# comms_uhf.net
KiCad netlist of a schematic drawn in Altium Designer
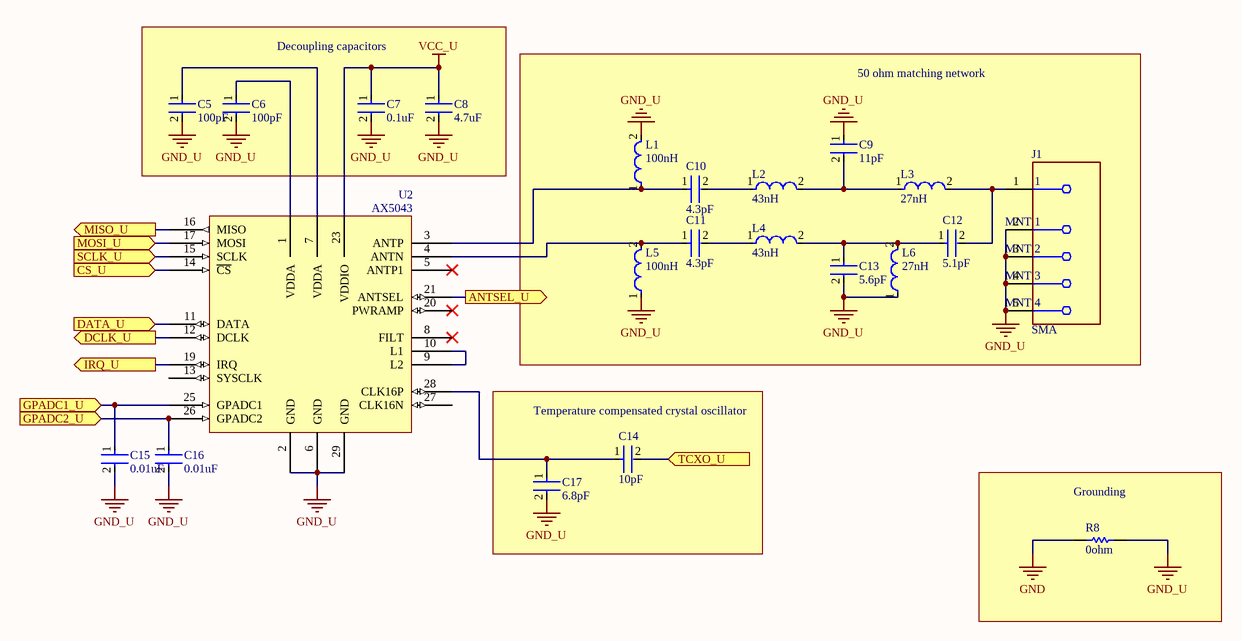
[diagram p0: comms_uhf.SchDoc]

(export (version "E")
  (design (tool "Eeschema 10.0.6"))
  (components
    (comp (ref "C5")
      (value "100pF")
      (footprint "FP-C0805C-DN-IPC_A")
      (description "Multilayer Ceramic Capacitors (MLCC) - SMD/SMT 100volts 100pF C0G 5%")
      (fields
        (field (name "MANUFACTURER") "KEMET")
        (field (name "MANUFACTURER PART NUMBER") "C0805C101J1GACTU")
      )
      (libsource (lib "WEST_Schematic_Library") (part "C0805C101J1GACTU"))
    )
    (comp (ref "C6")
      (value "100pF")
      (footprint "FP-C0805C-DN-IPC_A")
      (description "Multilayer Ceramic Capacitors (MLCC) - SMD/SMT 100volts 100pF C0G 5%")
      (fields
        (field (name "MANUFACTURER") "KEMET")
        (field (name "MANUFACTURER PART NUMBER") "C0805C101J1GACTU")
      )
      (libsource (lib "WEST_Schematic_Library") (part "C0805C101J1GACTU"))
    )
    (comp (ref "C7")
      (value "0.1uF")
      (footprint "FP-C0805C-DN-IPC_A")
      (description "Cap Ceramic 0.1uF 50V X7R 10% SMD 2.0 x 1.2 mm 125 C Paper T/R")
      (fields
        (field (name "MANUFACTURER") "KEMET")
        (field (name "MANUFACTURER PART NUMBER") "C0805C104K5RACTU")
      )
      (libsource (lib "WEST_Schematic_Library") (part "C0805C104K5RACTU"))
    )
    (comp (ref "C8")
      (value "4.7uF")
      (footprint "FP-C0805C-DN-IPC_A")
      (description "Cap Ceramic 4.7uF 25V X5R 10% SMD 0805 85°C Plastic T/R")
      (fields
        (field (name "MANUFACTURER") "KEMET")
        (field (name "MANUFACTURER PART NUMBER") "C0805C475K3PACTU")
      )
      (libsource (lib "WEST_Schematic_Library") (part "C0805C475K3PACTU"))
    )
    (comp (ref "C9")
      (value "11pF")
      (footprint "FP-C0805C-DN-IPC_A")
      (description "Cap Ceramic 11pF 50V C0G 5% SMD 0805 125°C Plastic T/R")
      (fields
        (field (name "MANUFACTURER") "KEMET")
        (field (name "MANUFACTURER PART NUMBER") "C0805C110J5GACTU")
      )
      (libsource (lib "WEST_Schematic_Library") (part "C0805C110J5GACTU"))
    )
    (comp (ref "C10")
      (value "4.3pF")
      (footprint "FP-C0805C-DN-IPC_A")
      (description "Cap Ceramic 4.3pF 100V C0G 0.5pF SMD 0805 125°C Paper T/R")
      (fields
        (field (name "MANUFACTURER") "KEMET")
        (field (name "MANUFACTURER PART NUMBER") "C0805C439D1GACTU")
      )
      (libsource (lib "WEST_Schematic_Library") (part "C0805C439D1GACTU"))
    )
    (comp (ref "C11")
      (value "4.3pF")
      (footprint "FP-C0805C-DN-IPC_A")
      (description "Cap Ceramic 4.3pF 100V C0G 0.5pF SMD 0805 125°C Paper T/R")
      (fields
        (field (name "MANUFACTURER") "KEMET")
        (field (name "MANUFACTURER PART NUMBER") "C0805C439D1GACTU")
      )
      (libsource (lib "WEST_Schematic_Library") (part "C0805C439D1GACTU"))
    )
    (comp (ref "C12")
      (value "5.1pF")
      (footprint "FP-C0805C-DN-IPC_A")
      (description "Cap Ceramic 5.1pF 50V C0G 0.25pF SMD 0805 125°C Paper T/R")
      (fields
        (field (name "MANUFACTURER") "KEMET")
        (field (name "MANUFACTURER PART NUMBER") "C0805C519C5GACTU")
      )
      (libsource (lib "WEST_Schematic_Library") (part "C0805C519C5GACTU"))
    )
    (comp (ref "C13")
      (value "5.6pF")
      (footprint "FP-C0805C-DN-IPC_A")
      (description "Cap Ceramic 5.6pF 50V C0G 0.5pF SMD 0805 125°C Plastic T/R")
      (fields
        (field (name "MANUFACTURER") "KEMET")
        (field (name "MANUFACTURER PART NUMBER") "C0805C569D5GACTU")
      )
      (libsource (lib "WEST_Schematic_Library") (part "C0805C569D5GACTU"))
    )
    (comp (ref "C14")
      (value "10pF")
      (footprint "FP-C0805C-DN-IPC_A")
      (description "Cap Ceramic 10pF 100V C0G 5% SMD 0805 125C Plastic T/R")
      (fields
        (field (name "MANUFACTURER") "KEMET")
        (field (name "MANUFACTURER PART NUMBER") "C0805C100J1GACTU")
      )
      (libsource (lib "WEST_Schematic_Library") (part "C0805C100J1GACTU"))
    )
    (comp (ref "C15")
      (value "0.01uF")
      (footprint "FP-C0805C-DN-IPC_A")
      (description "Cap Ceramic 0.01uF 50V X7R 10% SMD 0805 125C Plastic T/R")
      (fields
        (field (name "MANUFACTURER") "KEMET")
        (field (name "MANUFACTURER PART NUMBER") "C0805C103K5RAC-TU")
      )
      (libsource (lib "WEST_Schematic_Library") (part "C0805C103K5RAC-TU"))
    )
    (comp (ref "C16")
      (value "0.01uF")
      (footprint "FP-C0805C-DN-IPC_A")
      (description "Cap Ceramic 0.01uF 50V X7R 10% SMD 0805 125C Plastic T/R")
      (fields
        (field (name "MANUFACTURER") "KEMET")
        (field (name "MANUFACTURER PART NUMBER") "C0805C103K5RAC-TU")
      )
      (libsource (lib "WEST_Schematic_Library") (part "C0805C103K5RAC-TU"))
    )
    (comp (ref "C17")
      (value "6.8pF")
      (footprint "FP-C0805C-DN-IPC_A")
      (description "Cap Ceramic 6.8pF 50V C0G 0.5pF SMD 0805 125°C Plastic T/R")
      (fields
        (field (name "MANUFACTURER") "KEMET")
        (field (name "MANUFACTURER PART NUMBER") "C0805C689D5GACTU")
      )
      (libsource (lib "WEST_Schematic_Library") (part "C0805C689D5GACTU"))
    )
    (comp (ref "J1")
      (value "SMA")
      (footprint "FP-73251-1350-MFG")
      (description "RF Connectors / Coaxial Connectors SMA ST PCB-JCK STD SMT")
      (fields (field (name "MANUFACTURER") "Molex") (field (name "MANUFACTURER PART NUMBER") "73251-1350"))
      (libsource (lib "WEST_Schematic_Library") (part "73251-1350"))
    )
    (comp (ref "L1")
      (value "100nH")
      (footprint "FP-C0805C-DN-IPC_A")
      (description "Ind RF Chip Wirewound 100nH 5% 150MHz 65Q-Factor 400mA 0805 Embossed T/R")
      (fields
        (field (name "MANUFACTURER") "Murata")
        (field (name "MANUFACTURER PART NUMBER") "LQW2BASR10J00L")
      )
      (libsource (lib "WEST_Schematic_Library") (part "LQW2BASR10J00L"))
    )
    (comp (ref "L2")
      (value "43nH")
      (footprint "FP-C0805C-DN-IPC_A")
      (description "Ind RF Chip Wirewound 43nH 5% 200MHz 60Q-Factor 500mA 0805 Embossed T/R")
      (fields
        (field (name "MANUFACTURER") "Murata")
        (field (name "MANUFACTURER PART NUMBER") "LQW2BAS43NJ00L")
      )
      (libsource (lib "WEST_Schematic_Library") (part "LQW2BAS43NJ00L"))
    )
    (comp (ref "L3")
      (value "27nH")
      (footprint "FP-C0805C-DN-IPC_A")
      (description "Ind RF Chip Wirewound 27nH 0.5A ±5% 0805")
      (fields
        (field (name "MANUFACTURER") "Murata")
        (field (name "MANUFACTURER PART NUMBER") "LQW2BAS27NJ00L")
      )
      (libsource (lib "WEST_Schematic_Library") (part "LQW2BAS27NJ00L"))
    )
    (comp (ref "L4")
      (value "43nH")
      (footprint "FP-C0805C-DN-IPC_A")
      (description "Ind RF Chip Wirewound 43nH 5% 200MHz 60Q-Factor 500mA 0805 Embossed T/R")
      (fields
        (field (name "MANUFACTURER") "Murata")
        (field (name "MANUFACTURER PART NUMBER") "LQW2BAS43NJ00L")
      )
      (libsource (lib "WEST_Schematic_Library") (part "LQW2BAS43NJ00L"))
    )
    (comp (ref "L5")
      (value "100nH")
      (footprint "FP-C0805C-DN-IPC_A")
      (description "Ind RF Chip Wirewound 100nH 5% 150MHz 65Q-Factor 400mA 0805 Embossed T/R")
      (fields
        (field (name "MANUFACTURER") "Murata")
        (field (name "MANUFACTURER PART NUMBER") "LQW2BASR10J00L")
      )
      (libsource (lib "WEST_Schematic_Library") (part "LQW2BASR10J00L"))
    )
    (comp (ref "L6")
      (value "27nH")
      (footprint "FP-C0805C-DN-IPC_A")
      (description "Ind RF Chip Wirewound 27nH 0.5A ±5% 0805")
      (fields
        (field (name "MANUFACTURER") "Murata")
        (field (name "MANUFACTURER PART NUMBER") "LQW2BAS27NJ00L")
      )
      (libsource (lib "WEST_Schematic_Library") (part "LQW2BAS27NJ00L"))
    )
    (comp (ref "R8")
      (value "0ohm")
      (footprint "FP-C0805C-DN-IPC_A")
      (description "CRCW Series 0805 0.125 W 0 Ohm Jumper Surface Mount Thick Film Chip Resistor")
      (fields
        (field (name "MANUFACTURER") "Vishay")
        (field (name "MANUFACTURER PART NUMBER") "CRCW08050000Z0EA")
      )
      (libsource (lib "WEST_Schematic_Library") (part "CRCW08050000Z0EA"))
    )
    (comp (ref "U2")
      (value "AX5043")
      (footprint "QFN50P500X500X90_HS-29N")
      (description "Rf Transceiver ASK/AFSK/FM/FSK/4-FSK/GFSK/GMSK/MSK/PSK 1.8 V to 3.6V 28-PIN QFN T/r")
      (fields
        (field (name "MANUFACTURER") "ON Semiconductor")
        (field (name "MANUFACTURER PART NUMBER") "AX5043-1-TW30")
      )
      (libsource (lib "WEST_Schematic_Library") (part "AX5043-1-TW30"))
    )
  )
  (nets
    (net (code "1") (name "/ANTSEL_U") (class "Default")
      (node (ref "U2") (pin "21") (pinfunction "ANTSEL_21") (pintype "bidirectional"))
    )
    (net (code "2") (name "/CS_U") (class "Default")
      (node (ref "U2") (pin "14") (pinfunction "~{CS}_14") (pintype "input"))
    )
    (net (code "3") (name "/DATA_U") (class "Default")
      (node (ref "U2") (pin "11") (pinfunction "DATA_11") (pintype "bidirectional"))
    )
    (net (code "4") (name "/DCLK_U") (class "Default")
      (node (ref "U2") (pin "12") (pinfunction "DCLK_12") (pintype "bidirectional"))
    )
    (net (code "5") (name "/GPADC1_U") (class "Default")
      (node (ref "C15") (pin "1") (pinfunction "1_1") (pintype "passive"))
      (node (ref "U2") (pin "25") (pinfunction "GPADC1_25") (pintype "input"))
    )
    (net (code "6") (name "/GPADC2_U") (class "Default")
      (node (ref "C16") (pin "1") (pinfunction "1_1") (pintype "passive"))
      (node (ref "U2") (pin "26") (pinfunction "GPADC2_26") (pintype "input"))
    )
    (net (code "7") (name "/IRQ_U") (class "Default")
      (node (ref "U2") (pin "19") (pinfunction "IRQ_19") (pintype "bidirectional"))
    )
    (net (code "8") (name "/MISO_U") (class "Default")
      (node (ref "U2") (pin "16") (pinfunction "MISO_16") (pintype "output"))
    )
    (net (code "9") (name "/MOSI_U") (class "Default")
      (node (ref "U2") (pin "17") (pinfunction "MOSI_17") (pintype "input"))
    )
    (net (code "10") (name "/SCLK_U") (class "Default")
      (node (ref "U2") (pin "15") (pinfunction "SCLK_15") (pintype "input"))
    )
    (net (code "11") (name "/TCXO_U") (class "Default")
      (node (ref "C14") (pin "2") (pinfunction "2_2") (pintype "passive"))
    )
    (net (code "12") (name "GND") (class "Default")
      (node (ref "R8") (pin "1") (pinfunction "1_1") (pintype "passive"))
    )
    (net (code "13") (name "GND_U") (class "Default")
      (node (ref "C13") (pin "2") (pinfunction "2_2") (pintype "passive"))
      (node (ref "C15") (pin "2") (pinfunction "2_2") (pintype "passive"))
      (node (ref "C16") (pin "2") (pinfunction "2_2") (pintype "passive"))
      (node (ref "C17") (pin "2") (pinfunction "2_2") (pintype "passive"))
      (node (ref "C5") (pin "2") (pinfunction "2_2") (pintype "passive"))
      (node (ref "C6") (pin "2") (pinfunction "2_2") (pintype "passive"))
      (node (ref "C7") (pin "2") (pinfunction "2_2") (pintype "passive"))
      (node (ref "C8") (pin "2") (pinfunction "2_2") (pintype "passive"))
      (node (ref "C9") (pin "1") (pinfunction "1_1") (pintype "passive"))
      (node (ref "J1") (pin "2") (pinfunction "MNT_1_2") (pintype "passive"))
      (node (ref "J1") (pin "3") (pinfunction "MNT_2_3") (pintype "passive"))
      (node (ref "J1") (pin "4") (pinfunction "MNT_3_4") (pintype "passive"))
      (node (ref "J1") (pin "5") (pinfunction "MNT_4_5") (pintype "passive"))
      (node (ref "L1") (pin "2") (pinfunction "2_2") (pintype "passive"))
      (node (ref "L5") (pin "1") (pinfunction "1_1") (pintype "passive"))
      (node (ref "L6") (pin "1") (pinfunction "1_1") (pintype "passive"))
      (node (ref "R8") (pin "2") (pinfunction "2_2") (pintype "passive"))
      (node (ref "U2") (pin "2") (pinfunction "GND_2") (pintype "power_in"))
      (node (ref "U2") (pin "29") (pinfunction "GND_29") (pintype "power_in"))
      (node (ref "U2") (pin "6") (pinfunction "GND_6") (pintype "power_in"))
    )
    (net (code "14") (name "Net-(C5-Pad1)") (class "Default")
      (node (ref "C5") (pin "1") (pinfunction "1_1") (pintype "passive"))
      (node (ref "U2") (pin "7") (pinfunction "VDDA_7") (pintype "power_in"))
    )
    (net (code "15") (name "Net-(C6-Pad1)") (class "Default")
      (node (ref "C6") (pin "1") (pinfunction "1_1") (pintype "passive"))
      (node (ref "U2") (pin "1") (pinfunction "VDDA_1") (pintype "power_in"))
    )
    (net (code "16") (name "Net-(C9-Pad2)") (class "Default")
      (node (ref "C9") (pin "2") (pinfunction "2_2") (pintype "passive"))
      (node (ref "L2") (pin "2") (pinfunction "2_2") (pintype "passive"))
      (node (ref "L3") (pin "1") (pinfunction "1_1") (pintype "passive"))
    )
    (net (code "17") (name "Net-(C10-Pad2)") (class "Default")
      (node (ref "C10") (pin "2") (pinfunction "2_2") (pintype "passive"))
      (node (ref "L2") (pin "1") (pinfunction "1_1") (pintype "passive"))
    )
    (net (code "18") (name "Net-(C11-Pad2)") (class "Default")
      (node (ref "C11") (pin "2") (pinfunction "2_2") (pintype "passive"))
      (node (ref "L4") (pin "1") (pinfunction "1_1") (pintype "passive"))
    )
    (net (code "19") (name "Net-(C12-Pad1)") (class "Default")
      (node (ref "C12") (pin "1") (pinfunction "1_1") (pintype "passive"))
      (node (ref "C13") (pin "1") (pinfunction "1_1") (pintype "passive"))
      (node (ref "L4") (pin "2") (pinfunction "2_2") (pintype "passive"))
      (node (ref "L6") (pin "2") (pinfunction "2_2") (pintype "passive"))
    )
    (net (code "20") (name "Net-(C12-Pad2)") (class "Default")
      (node (ref "C12") (pin "2") (pinfunction "2_2") (pintype "passive"))
      (node (ref "J1") (pin "1") (pinfunction "1_1") (pintype "passive"))
      (node (ref "L3") (pin "2") (pinfunction "2_2") (pintype "passive"))
    )
    (net (code "21") (name "Net-(U2-ANTN)") (class "Default")
      (node (ref "C11") (pin "1") (pinfunction "1_1") (pintype "passive"))
      (node (ref "L5") (pin "2") (pinfunction "2_2") (pintype "passive"))
      (node (ref "U2") (pin "4") (pinfunction "ANTN_4") (pintype "passive"))
    )
    (net (code "22") (name "Net-(U2-ANTP)") (class "Default")
      (node (ref "C10") (pin "1") (pinfunction "1_1") (pintype "passive"))
      (node (ref "L1") (pin "1") (pinfunction "1_1") (pintype "passive"))
      (node (ref "U2") (pin "3") (pinfunction "ANTP_3") (pintype "passive"))
    )
    (net (code "23") (name "Net-(U2-CLK16P)") (class "Default")
      (node (ref "C14") (pin "1") (pinfunction "1_1") (pintype "passive"))
      (node (ref "C17") (pin "1") (pinfunction "1_1") (pintype "passive"))
      (node (ref "U2") (pin "28") (pinfunction "CLK16P_28") (pintype "bidirectional"))
    )
    (net (code "24") (name "Net-(U2-L1)") (class "Default")
      (node (ref "U2") (pin "10") (pinfunction "L1_10") (pintype "passive"))
      (node (ref "U2") (pin "9") (pinfunction "L2_9") (pintype "passive"))
    )
    (net (code "25") (name "VCC_U") (class "Default")
      (node (ref "C7") (pin "1") (pinfunction "1_1") (pintype "passive"))
      (node (ref "C8") (pin "1") (pinfunction "1_1") (pintype "passive"))
      (node (ref "U2") (pin "23") (pinfunction "VDDIO_23") (pintype "power_in"))
    )
    (net (code "26") (name "unconnected-(U2-ANTP1-Pad5)") (class "Default")
      (node (ref "U2") (pin "5") (pinfunction "ANTP1_5") (pintype "power_in+no_connect"))
    )
    (net (code "27") (name "unconnected-(U2-CLK16N-Pad27)") (class "Default")
      (node (ref "U2") (pin "27") (pinfunction "CLK16N_27") (pintype "bidirectional"))
    )
    (net (code "28") (name "unconnected-(U2-FILT-Pad8)") (class "Default")
      (node (ref "U2") (pin "8") (pinfunction "FILT_8") (pintype "passive+no_connect"))
    )
    (net (code "29") (name "unconnected-(U2-PWRAMP-Pad20)") (class "Default")
      (node (ref "U2") (pin "20") (pinfunction "PWRAMP_20") (pintype "bidirectional+no_connect"))
    )
    (net (code "30") (name "unconnected-(U2-SYSCLK-Pad13)") (class "Default")
      (node (ref "U2") (pin "13") (pinfunction "SYSCLK_13") (pintype "bidirectional"))
    )
  )
)
